# zerog_accelerometer_featherwing.net
KiCad netlist of a schematic drawn in EAGLE
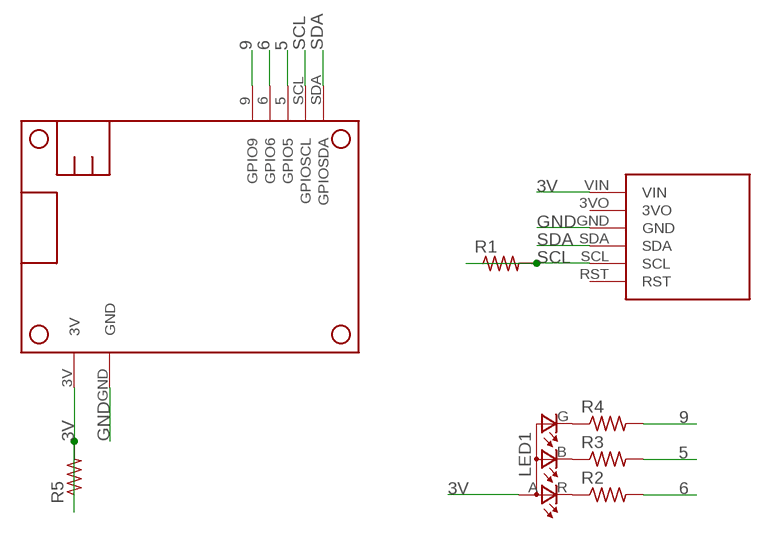
[diagram p0: schematic, sheet 1]

(export (version "E")
  (design (tool "Eeschema 10.0.6"))
  (components
    (comp (ref "LED1")
      (value "LEDRGBOLD")
      (footprint "eagle-import:P-LCC-4-3")
      (libsource (lib "eagle-import") (part "LEDRGBOLD"))
    )
    (comp (ref "R1")
      (value "RES-US1206FAB")
      (footprint "eagle-import:R1206FAB")
      (libsource (lib "eagle-import") (part "RES-US1206FAB"))
    )
    (comp (ref "R2")
      (value "RES-US1206FAB")
      (footprint "eagle-import:R1206FAB")
      (libsource (lib "eagle-import") (part "RES-US1206FAB"))
    )
    (comp (ref "R3")
      (value "RES-US1206FAB")
      (footprint "eagle-import:R1206FAB")
      (libsource (lib "eagle-import") (part "RES-US1206FAB"))
    )
    (comp (ref "R4")
      (value "RES-US1206FAB")
      (footprint "eagle-import:R1206FAB")
      (libsource (lib "eagle-import") (part "RES-US1206FAB"))
    )
    (comp (ref "R5")
      (value "RES-US1206FAB")
      (footprint "eagle-import:R1206FAB")
      (libsource (lib "eagle-import") (part "RES-US1206FAB"))
    )
    (comp (ref "U$1")
      (value "FEATHERWING_I2C")
      (footprint "eagle-import:FEATHERWING_I2C")
      (libsource (lib "eagle-import") (part "FEATHERWING_I2C"))
    )
    (comp (ref "U$2")
      (value "BNO055_BREAKOUT")
      (footprint "eagle-import:BNO055_BREAKOUT")
      (libsource (lib "eagle-import") (part "BNO055_BREAKOUT"))
    )
  )
  (nets
    (net (code "1") (name "/3V") (class "Default")
      (node (ref "LED1") (pin "A") (pinfunction "A2_A") (pintype "passive"))
      (node (ref "R5") (pin "1") (pinfunction "1_1") (pintype "passive"))
      (node (ref "R5") (pin "2") (pinfunction "2_2") (pintype "passive"))
      (node (ref "U$1") (pin "3V") (pinfunction "3V_3V") (pintype "power_in"))
      (node (ref "U$2") (pin "VIN") (pinfunction "VIN_VIN") (pintype "bidirectional"))
    )
    (net (code "2") (name "/5") (class "Default")
      (node (ref "R3") (pin "2") (pinfunction "2_2") (pintype "passive"))
      (node (ref "U$1") (pin "5") (pinfunction "GPIO5_5") (pintype "bidirectional"))
    )
    (net (code "3") (name "/6") (class "Default")
      (node (ref "R2") (pin "2") (pinfunction "2_2") (pintype "passive"))
      (node (ref "U$1") (pin "6") (pinfunction "GPIO6_6") (pintype "bidirectional"))
    )
    (net (code "4") (name "/9") (class "Default")
      (node (ref "R4") (pin "2") (pinfunction "2_2") (pintype "passive"))
      (node (ref "U$1") (pin "9") (pinfunction "GPIO9_9") (pintype "bidirectional"))
    )
    (net (code "5") (name "/GND") (class "Default")
      (node (ref "U$1") (pin "GND") (pinfunction "GND_GND") (pintype "power_in"))
      (node (ref "U$2") (pin "GND") (pinfunction "GND_GND") (pintype "bidirectional"))
    )
    (net (code "6") (name "/SCL") (class "Default")
      (node (ref "R1") (pin "1") (pinfunction "1_1") (pintype "passive"))
      (node (ref "R1") (pin "2") (pinfunction "2_2") (pintype "passive"))
      (node (ref "U$1") (pin "SCL") (pinfunction "GPIOSCL_SCL") (pintype "bidirectional"))
      (node (ref "U$2") (pin "SCL") (pinfunction "SCL_SCL") (pintype "bidirectional"))
    )
    (net (code "7") (name "/SDA") (class "Default")
      (node (ref "U$1") (pin "SDA") (pinfunction "GPIOSDA_SDA") (pintype "bidirectional"))
      (node (ref "U$2") (pin "SDA") (pinfunction "SDA_SDA") (pintype "bidirectional"))
    )
    (net (code "8") (name "Net-(LED1-CBLUE)") (class "Default")
      (node (ref "LED1") (pin "B") (pinfunction "CBLUE_B") (pintype "passive"))
      (node (ref "R3") (pin "1") (pinfunction "1_1") (pintype "passive"))
    )
    (net (code "9") (name "Net-(LED1-CGREEN)") (class "Default")
      (node (ref "LED1") (pin "G") (pinfunction "CGREEN_G") (pintype "passive"))
      (node (ref "R4") (pin "1") (pinfunction "1_1") (pintype "passive"))
    )
    (net (code "10") (name "Net-(LED1-CRED)") (class "Default")
      (node (ref "LED1") (pin "R") (pinfunction "CRED_R") (pintype "passive"))
      (node (ref "R2") (pin "1") (pinfunction "1_1") (pintype "passive"))
    )
    (net (code "11") (name "unconnected-(U$2-Pad3VO)") (class "Default")
      (node (ref "U$2") (pin "3VO") (pinfunction "3VO_3VO") (pintype "bidirectional"))
    )
    (net (code "12") (name "unconnected-(U$2-PadRST)") (class "Default")
      (node (ref "U$2") (pin "RST") (pinfunction "RST_RST") (pintype "bidirectional"))
    )
  )
)
